# PWR.net
KiCad netlist of a schematic drawn in Altium Designer
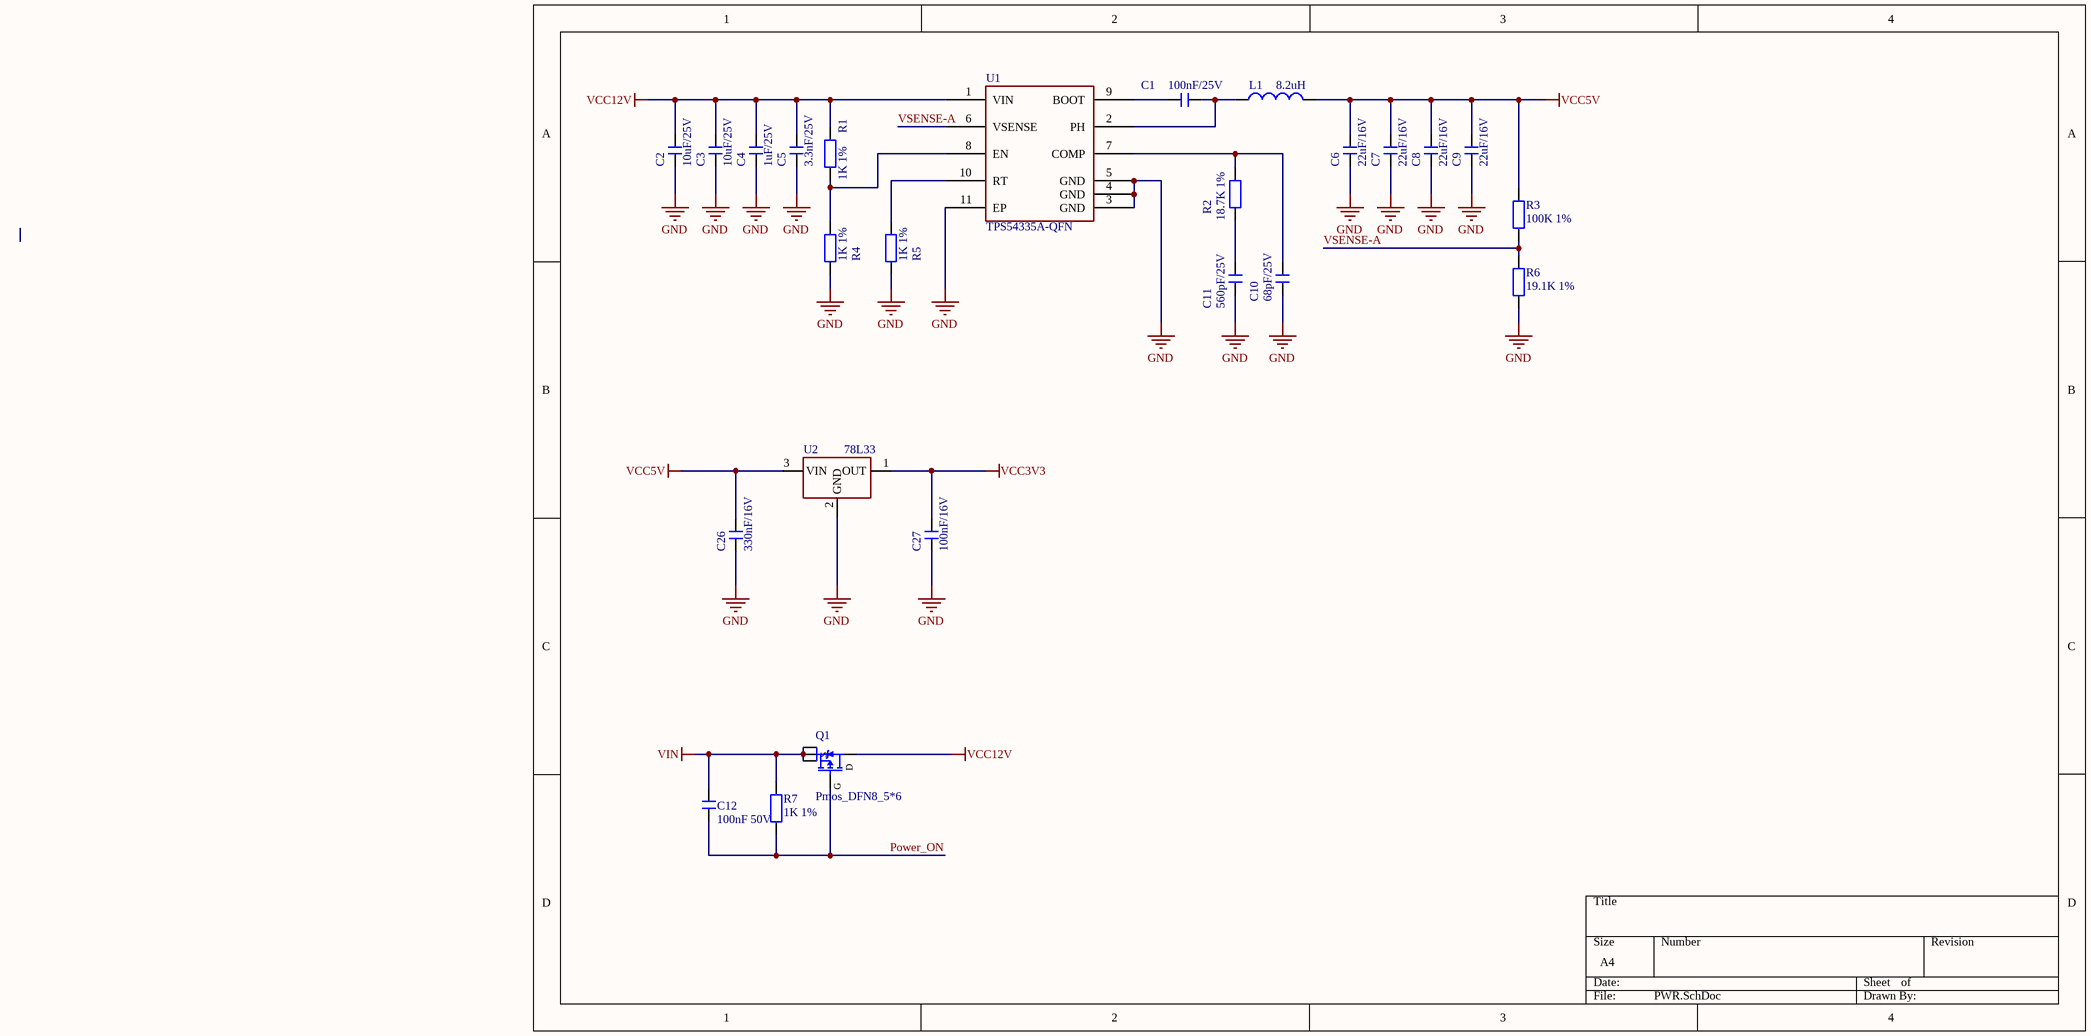
[diagram p0: PWR.SchDoc]

(export (version "E")
  (design (tool "Eeschema 10.0.6"))
  (components
    (comp (ref "C1")
      (value "100nF/25V")
      (footprint "c0603_l")
      (description "无极性贴片电容")
      (fields (field (name "版权归属") "源创客"))
      (libsource (lib "Capacitor") (part "C"))
    )
    (comp (ref "C2")
      (value "10uF/25V")
      (footprint "c0603_l")
      (description "无极性贴片电容")
      (fields (field (name "版权归属") "源创客"))
      (libsource (lib "Capacitor") (part "C"))
    )
    (comp (ref "C3")
      (value "10uF/25V")
      (footprint "c0603_l")
      (description "无极性贴片电容")
      (fields (field (name "版权归属") "源创客"))
      (libsource (lib "Capacitor") (part "C"))
    )
    (comp (ref "C4")
      (value "1uF/25V")
      (footprint "c0603_l")
      (description "无极性贴片电容")
      (fields (field (name "版权归属") "源创客"))
      (libsource (lib "Capacitor") (part "C"))
    )
    (comp (ref "C5")
      (value "3.3nF/25V")
      (footprint "c0603_l")
      (description "无极性贴片电容")
      (fields (field (name "版权归属") "源创客"))
      (libsource (lib "Capacitor") (part "C"))
    )
    (comp (ref "C6")
      (value "22uF/16V")
      (footprint "c0603_l")
      (description "无极性贴片电容")
      (fields (field (name "版权归属") "源创客"))
      (libsource (lib "Capacitor") (part "C"))
    )
    (comp (ref "C7")
      (value "22uF/16V")
      (footprint "c0603_l")
      (description "无极性贴片电容")
      (fields (field (name "版权归属") "源创客"))
      (libsource (lib "Capacitor") (part "C"))
    )
    (comp (ref "C8")
      (value "22uF/16V")
      (footprint "c0603_l")
      (description "无极性贴片电容")
      (fields (field (name "版权归属") "源创客"))
      (libsource (lib "Capacitor") (part "C"))
    )
    (comp (ref "C9")
      (value "22uF/16V")
      (footprint "c0603_l")
      (description "无极性贴片电容")
      (fields (field (name "版权归属") "源创客"))
      (libsource (lib "Capacitor") (part "C"))
    )
    (comp (ref "C10")
      (value "68pF/25V")
      (footprint "c0603_l")
      (description "无极性贴片电容")
      (fields (field (name "版权归属") "源创客"))
      (libsource (lib "Capacitor") (part "C"))
    )
    (comp (ref "C11")
      (value "560pF/25V")
      (footprint "c0603_l")
      (description "无极性贴片电容")
      (fields (field (name "版权归属") "源创客"))
      (libsource (lib "Capacitor") (part "C"))
    )
    (comp (ref "C12")
      (value "100nF 50V")
      (footprint "c0603_l")
      (description "无极性贴片电容")
      (fields (field (name "版权归属") "源创客"))
      (libsource (lib "Capacitor") (part "C"))
    )
    (comp (ref "C26")
      (value "330nF/16V")
      (footprint "c0603_l")
      (description "无极性贴片电容")
      (fields (field (name "版权归属") "源创客"))
      (libsource (lib "Capacitor") (part "C"))
    )
    (comp (ref "C27")
      (value "100nF/16V")
      (footprint "c0603_l")
      (description "无极性贴片电容")
      (fields (field (name "版权归属") "源创客"))
      (libsource (lib "Capacitor") (part "C"))
    )
    (comp (ref "L1")
      (value "8.2uH")
      (footprint "NR4020")
      (description "小功率贴片电感")
      (fields (field (name "版权归属") "源创客"))
      (libsource (lib "Inductor") (part "L"))
    )
    (comp (ref "Q1")
      (value "Pmos_DFN8_5*6")
      (footprint "DFN8_5*6")
      (fields (field (name "版权归属") "源创客"))
      (libsource (lib "MOSFET BJT IGBT") (part "Pmos_DFN8_5*6"))
    )
    (comp (ref "R1")
      (value "1K 1%")
      (footprint "r0603_l")
      (description "贴片电阻")
      (fields (field (name "版权归属") "源创客"))
      (libsource (lib "Resistor") (part "R"))
    )
    (comp (ref "R2")
      (value "18.7K 1%")
      (footprint "r0603_l")
      (description "贴片电阻")
      (fields (field (name "版权归属") "源创客"))
      (libsource (lib "Resistor") (part "R"))
    )
    (comp (ref "R3")
      (value "100K 1%")
      (footprint "r0603_l")
      (description "贴片电阻")
      (fields (field (name "版权归属") "源创客"))
      (libsource (lib "Resistor") (part "R"))
    )
    (comp (ref "R4")
      (value "1K 1%")
      (footprint "r0603_l")
      (description "贴片电阻")
      (fields (field (name "版权归属") "源创客"))
      (libsource (lib "Resistor") (part "R"))
    )
    (comp (ref "R5")
      (value "1K 1%")
      (footprint "r0603_l")
      (description "贴片电阻")
      (fields (field (name "版权归属") "源创客"))
      (libsource (lib "Resistor") (part "R"))
    )
    (comp (ref "R6")
      (value "19.1K 1%")
      (footprint "r0603_l")
      (description "贴片电阻")
      (fields (field (name "版权归属") "源创客"))
      (libsource (lib "Resistor") (part "R"))
    )
    (comp (ref "R7")
      (value "1K 1%")
      (footprint "r0603_l")
      (description "贴片电阻")
      (fields (field (name "版权归属") "源创客"))
      (libsource (lib "Resistor") (part "R"))
    )
    (comp (ref "U1")
      (value "TPS54335A-QFN")
      (footprint "VSON-10_L3.0-W3.0-P0.50-TL-EP")
      (description "BUCK")
      (libsource (lib "DCDC Convert") (part "TPS54335A-QFN"))
    )
    (comp (ref "U2") (value "78L33") (footprint "SOT89_L") (libsource (lib "LDO") (part "78L33")))
  )
  (nets
    (net (code "1") (name "/Power_ON") (class "Default")
      (node (ref "C12") (pin "2") (pinfunction "2_2") (pintype "passive"))
      (node (ref "Q1") (pin "4") (pinfunction "G_4") (pintype "passive"))
      (node (ref "R7") (pin "2") (pinfunction "2_2") (pintype "passive"))
    )
    (net (code "2") (name "/VSENSE-A") (class "Default")
      (node (ref "R3") (pin "2") (pinfunction "2_2") (pintype "passive"))
      (node (ref "R6") (pin "1") (pinfunction "1_1") (pintype "passive"))
      (node (ref "U1") (pin "6") (pinfunction "VSENSE_6") (pintype "passive"))
    )
    (net (code "3") (name "GND") (class "Default")
      (node (ref "C10") (pin "1") (pinfunction "1_1") (pintype "passive"))
      (node (ref "C11") (pin "1") (pinfunction "1_1") (pintype "passive"))
      (node (ref "C2") (pin "1") (pinfunction "1_1") (pintype "passive"))
      (node (ref "C26") (pin "1") (pinfunction "1_1") (pintype "passive"))
      (node (ref "C27") (pin "1") (pinfunction "1_1") (pintype "passive"))
      (node (ref "C3") (pin "1") (pinfunction "1_1") (pintype "passive"))
      (node (ref "C4") (pin "1") (pinfunction "1_1") (pintype "passive"))
      (node (ref "C5") (pin "1") (pinfunction "1_1") (pintype "passive"))
      (node (ref "C6") (pin "1") (pinfunction "1_1") (pintype "passive"))
      (node (ref "C7") (pin "1") (pinfunction "1_1") (pintype "passive"))
      (node (ref "C8") (pin "1") (pinfunction "1_1") (pintype "passive"))
      (node (ref "C9") (pin "1") (pinfunction "1_1") (pintype "passive"))
      (node (ref "R4") (pin "2") (pinfunction "2_2") (pintype "passive"))
      (node (ref "R5") (pin "2") (pinfunction "2_2") (pintype "passive"))
      (node (ref "R6") (pin "2") (pinfunction "2_2") (pintype "passive"))
      (node (ref "U1") (pin "11") (pinfunction "EP_11") (pintype "passive"))
      (node (ref "U1") (pin "3") (pinfunction "GND_3") (pintype "passive"))
      (node (ref "U1") (pin "4") (pinfunction "GND_4") (pintype "passive"))
      (node (ref "U1") (pin "5") (pinfunction "GND_5") (pintype "passive"))
      (node (ref "U2") (pin "2") (pinfunction "GND_2") (pintype "passive"))
    )
    (net (code "4") (name "Net-(C11-Pad2)") (class "Default")
      (node (ref "C11") (pin "2") (pinfunction "2_2") (pintype "passive"))
      (node (ref "R2") (pin "2") (pinfunction "2_2") (pintype "passive"))
    )
    (net (code "5") (name "Net-(U1-BOOT)") (class "Default")
      (node (ref "C1") (pin "2") (pinfunction "2_2") (pintype "passive"))
      (node (ref "U1") (pin "9") (pinfunction "BOOT_9") (pintype "passive"))
    )
    (net (code "6") (name "Net-(U1-COMP)") (class "Default")
      (node (ref "C10") (pin "2") (pinfunction "2_2") (pintype "passive"))
      (node (ref "R2") (pin "1") (pinfunction "1_1") (pintype "passive"))
      (node (ref "U1") (pin "7") (pinfunction "COMP_7") (pintype "passive"))
    )
    (net (code "7") (name "Net-(U1-EN)") (class "Default")
      (node (ref "R1") (pin "2") (pinfunction "2_2") (pintype "passive"))
      (node (ref "R4") (pin "1") (pinfunction "1_1") (pintype "passive"))
      (node (ref "U1") (pin "8") (pinfunction "EN_8") (pintype "passive"))
    )
    (net (code "8") (name "Net-(U1-PH)") (class "Default")
      (node (ref "C1") (pin "1") (pinfunction "1_1") (pintype "passive"))
      (node (ref "L1") (pin "1") (pinfunction "1_1") (pintype "passive"))
      (node (ref "U1") (pin "2") (pinfunction "PH_2") (pintype "passive"))
    )
    (net (code "9") (name "Net-(U1-RT)") (class "Default")
      (node (ref "R5") (pin "1") (pinfunction "1_1") (pintype "passive"))
      (node (ref "U1") (pin "10") (pinfunction "RT_10") (pintype "passive"))
    )
    (net (code "10") (name "VCC3V3") (class "Default")
      (node (ref "C27") (pin "2") (pinfunction "2_2") (pintype "passive"))
      (node (ref "U2") (pin "1") (pinfunction "OUT_1") (pintype "passive"))
    )
    (net (code "11") (name "VCC5V") (class "Default")
      (node (ref "C26") (pin "2") (pinfunction "2_2") (pintype "passive"))
      (node (ref "C6") (pin "2") (pinfunction "2_2") (pintype "passive"))
      (node (ref "C7") (pin "2") (pinfunction "2_2") (pintype "passive"))
      (node (ref "C8") (pin "2") (pinfunction "2_2") (pintype "passive"))
      (node (ref "C9") (pin "2") (pinfunction "2_2") (pintype "passive"))
      (node (ref "L1") (pin "2") (pinfunction "2_2") (pintype "passive"))
      (node (ref "R3") (pin "1") (pinfunction "1_1") (pintype "passive"))
      (node (ref "U2") (pin "3") (pinfunction "VIN_3") (pintype "passive"))
    )
    (net (code "12") (name "VCC12V") (class "Default")
      (node (ref "C2") (pin "2") (pinfunction "2_2") (pintype "passive"))
      (node (ref "C3") (pin "2") (pinfunction "2_2") (pintype "passive"))
      (node (ref "C4") (pin "2") (pinfunction "2_2") (pintype "passive"))
      (node (ref "C5") (pin "2") (pinfunction "2_2") (pintype "passive"))
      (node (ref "Q1") (pin "5") (pinfunction "D_5") (pintype "passive"))
      (node (ref "R1") (pin "1") (pinfunction "1_1") (pintype "passive"))
      (node (ref "U1") (pin "1") (pinfunction "VIN_1") (pintype "passive"))
    )
    (net (code "13") (name "VIN") (class "Default")
      (node (ref "C12") (pin "1") (pinfunction "1_1") (pintype "passive"))
      (node (ref "Q1") (pin "1") (pinfunction "S_1") (pintype "passive"))
      (node (ref "Q1") (pin "2") (pinfunction "S_2") (pintype "passive"))
      (node (ref "Q1") (pin "3") (pinfunction "S_3") (pintype "passive"))
      (node (ref "R7") (pin "1") (pinfunction "1_1") (pintype "passive"))
    )
  )
)
